# aw_601_pongclock.net
KiCad netlist of a schematic drawn in EAGLE
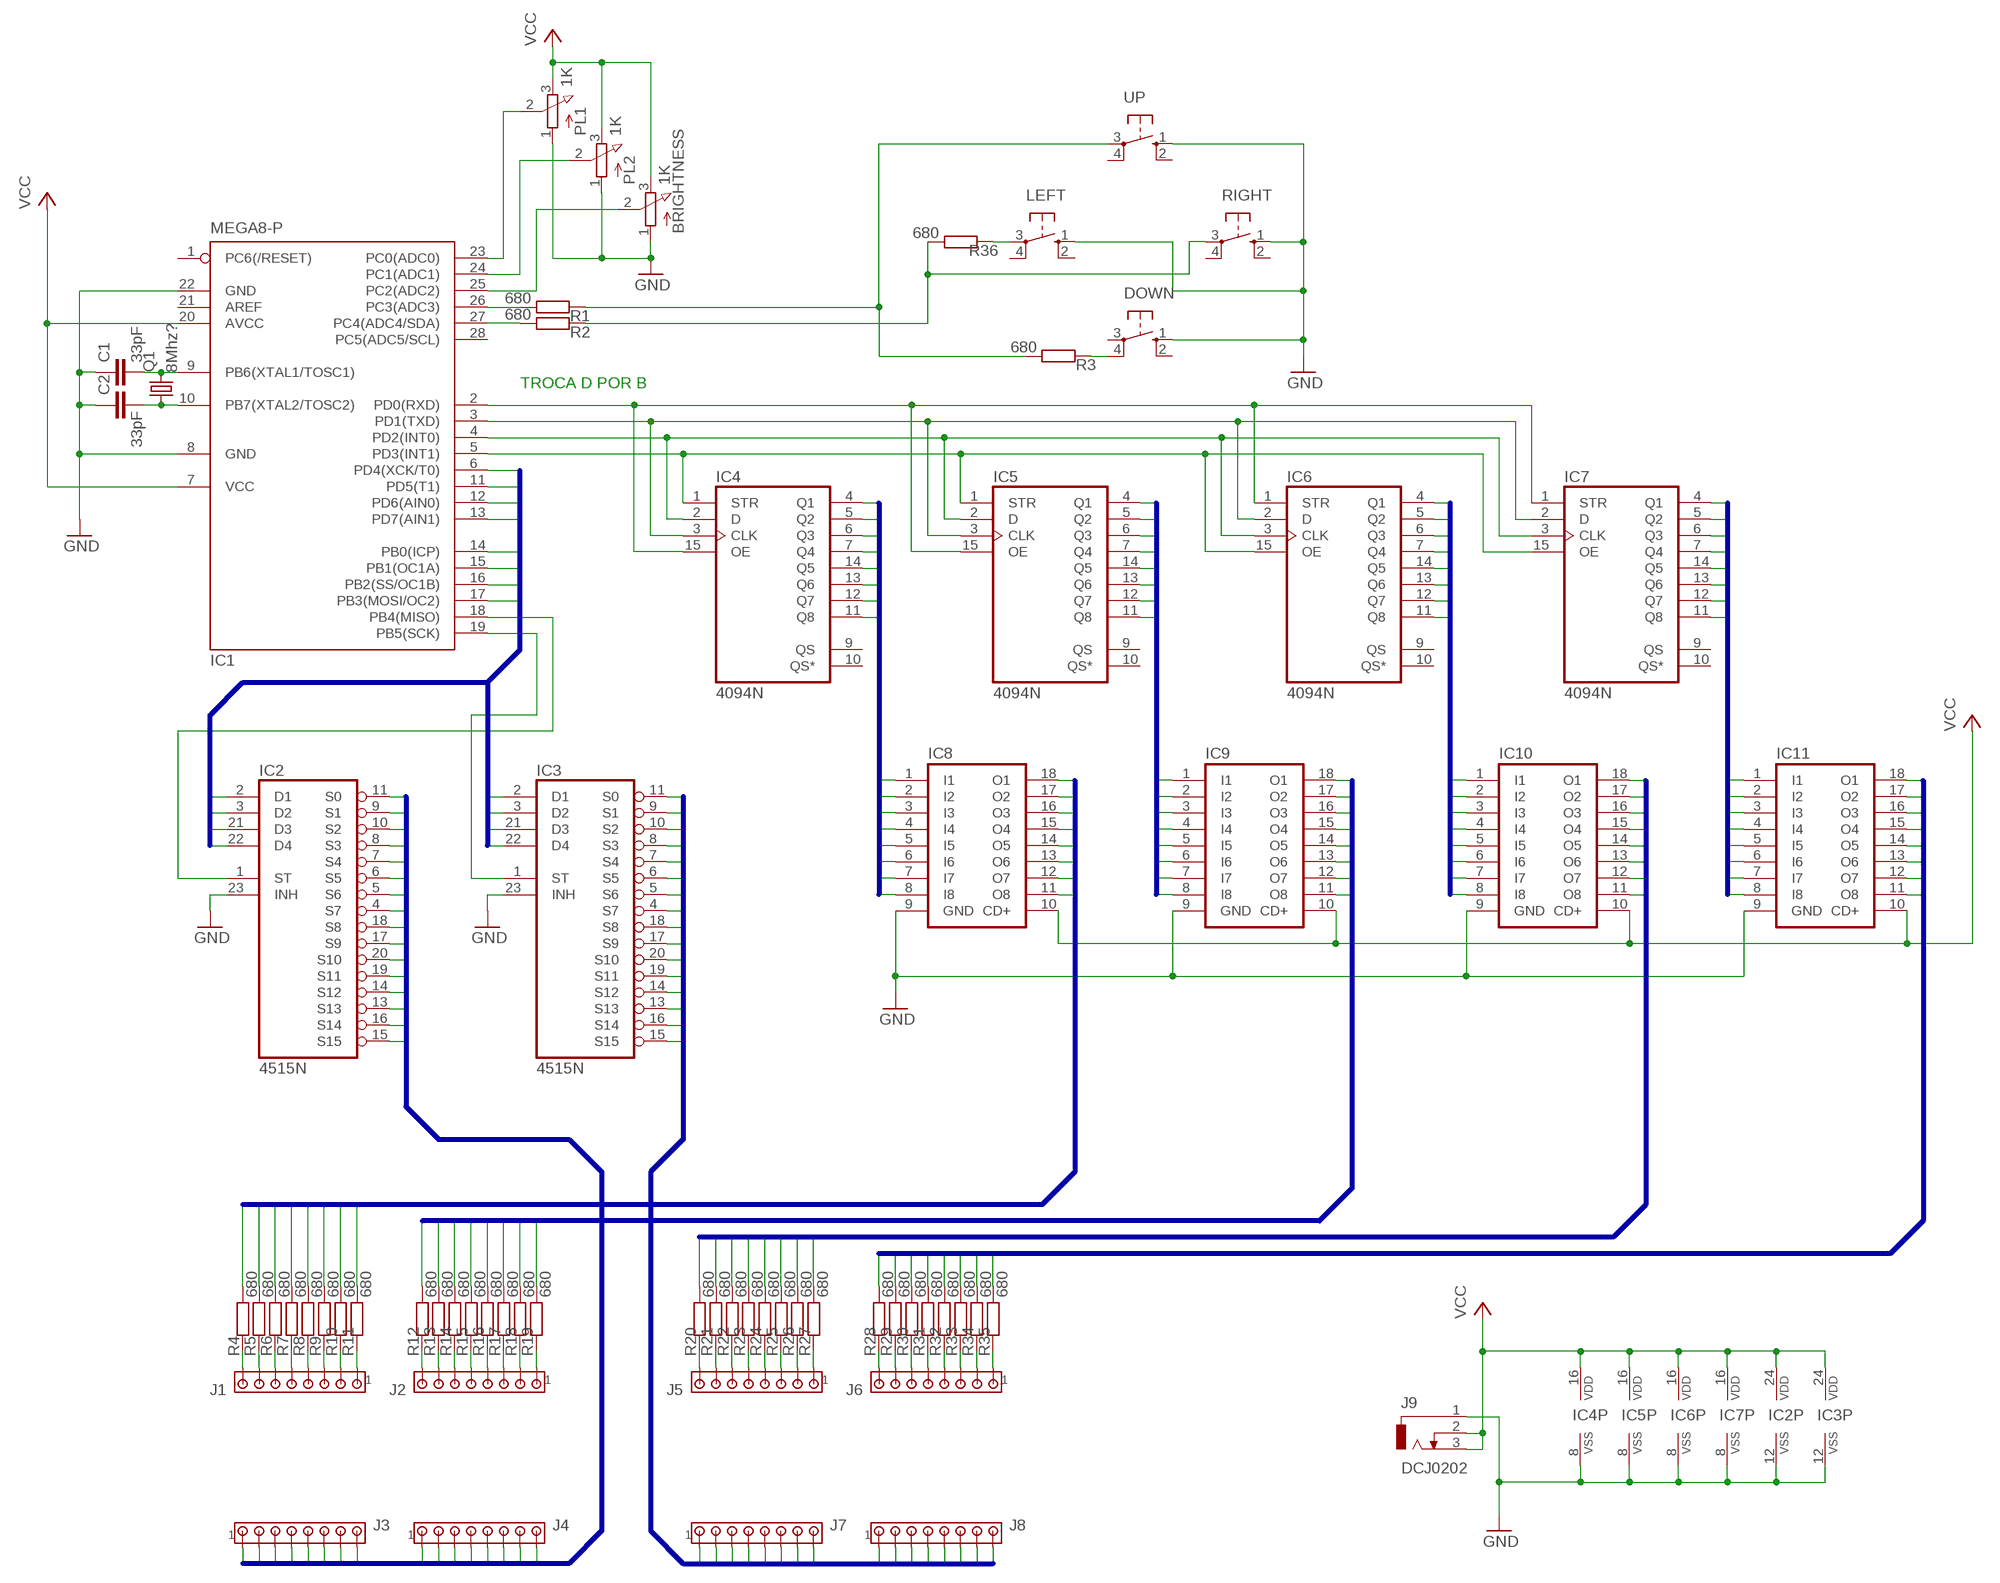
[diagram p0: schematic, sheet 1]

(export (version "E")
  (design (tool "Eeschema 10.0.6"))
  (components
    (comp (ref "BRIGHTNESS")
      (value "1K")
      (footprint "eagle-import:3RP_1610N")
      (libsource (lib "eagle-import") (part "3RP/1610N"))
    )
    (comp (ref "C1")
      (value "33pF")
      (footprint "eagle-import:C025-025X050")
      (libsource (lib "eagle-import") (part "C-EU025-025X050"))
    )
    (comp (ref "C2")
      (value "33pF")
      (footprint "eagle-import:C025-025X050")
      (libsource (lib "eagle-import") (part "C-EU025-025X050"))
    )
    (comp (ref "DOWN")
      (value "40/XX")
      (footprint "eagle-import:B3F_40XX")
      (libsource (lib "eagle-import") (part "40/XX"))
    )
    (comp (ref "IC1")
      (value "MEGA8-P")
      (footprint "eagle-import:DIL28-3")
      (libsource (lib "eagle-import") (part "MEGA8-P"))
    )
    (comp (ref "IC2")
      (value "4515N")
      (footprint "eagle-import:DIL24-6")
      (libsource (lib "eagle-import") (part "4515N"))
    )
    (comp (ref "IC3")
      (value "4515N")
      (footprint "eagle-import:DIL24-6")
      (libsource (lib "eagle-import") (part "4515N"))
    )
    (comp (ref "IC4")
      (value "4094N")
      (footprint "eagle-import:DIL16")
      (libsource (lib "eagle-import") (part "4094N"))
    )
    (comp (ref "IC5")
      (value "4094N")
      (footprint "eagle-import:DIL16")
      (libsource (lib "eagle-import") (part "4094N"))
    )
    (comp (ref "IC6")
      (value "4094N")
      (footprint "eagle-import:DIL16")
      (libsource (lib "eagle-import") (part "4094N"))
    )
    (comp (ref "IC7")
      (value "4094N")
      (footprint "eagle-import:DIL16")
      (libsource (lib "eagle-import") (part "4094N"))
    )
    (comp (ref "IC8")
      (value "ULN2803A")
      (footprint "eagle-import:DIL18")
      (libsource (lib "eagle-import") (part "ULN2803A"))
    )
    (comp (ref "IC9")
      (value "ULN2803A")
      (footprint "eagle-import:DIL18")
      (libsource (lib "eagle-import") (part "ULN2803A"))
    )
    (comp (ref "IC10")
      (value "ULN2803A")
      (footprint "eagle-import:DIL18")
      (libsource (lib "eagle-import") (part "ULN2803A"))
    )
    (comp (ref "IC11")
      (value "ULN2803A")
      (footprint "eagle-import:DIL18")
      (libsource (lib "eagle-import") (part "ULN2803A"))
    )
    (comp (ref "J1")
      (value "MTA08-100")
      (footprint "eagle-import:10X08MTA")
      (libsource (lib "eagle-import") (part "MTA08-100"))
    )
    (comp (ref "J2")
      (value "MTA08-100")
      (footprint "eagle-import:10X08MTA")
      (libsource (lib "eagle-import") (part "MTA08-100"))
    )
    (comp (ref "J3")
      (value "MTA08-100")
      (footprint "eagle-import:10X08MTA")
      (libsource (lib "eagle-import") (part "MTA08-100"))
    )
    (comp (ref "J4")
      (value "MTA08-100")
      (footprint "eagle-import:10X08MTA")
      (libsource (lib "eagle-import") (part "MTA08-100"))
    )
    (comp (ref "J5")
      (value "MTA08-100")
      (footprint "eagle-import:10X08MTA")
      (libsource (lib "eagle-import") (part "MTA08-100"))
    )
    (comp (ref "J6")
      (value "MTA08-100")
      (footprint "eagle-import:10X08MTA")
      (libsource (lib "eagle-import") (part "MTA08-100"))
    )
    (comp (ref "J7")
      (value "MTA08-100")
      (footprint "eagle-import:10X08MTA")
      (libsource (lib "eagle-import") (part "MTA08-100"))
    )
    (comp (ref "J8")
      (value "MTA08-100")
      (footprint "eagle-import:10X08MTA")
      (libsource (lib "eagle-import") (part "MTA08-100"))
    )
    (comp (ref "J9")
      (value "DCJ0202")
      (footprint "eagle-import:DCJ0202")
      (libsource (lib "eagle-import") (part "DCJ0202"))
    )
    (comp (ref "LEFT")
      (value "40/XX")
      (footprint "eagle-import:B3F_40XX")
      (libsource (lib "eagle-import") (part "40/XX"))
    )
    (comp (ref "PL1")
      (value "1K")
      (footprint "eagle-import:3RP_1610N")
      (libsource (lib "eagle-import") (part "3RP/1610N"))
    )
    (comp (ref "PL2")
      (value "1K")
      (footprint "eagle-import:3RP_1610N")
      (libsource (lib "eagle-import") (part "3RP/1610N"))
    )
    (comp (ref "Q1")
      (value "8Mhz?")
      (footprint "eagle-import:HC49U70")
      (libsource (lib "eagle-import") (part "CRYSTALHC49U70"))
    )
    (comp (ref "R1")
      (value "680")
      (footprint "eagle-import:0207_10")
      (libsource (lib "eagle-import") (part "R-EU_0207/10"))
    )
    (comp (ref "R2")
      (value "680")
      (footprint "eagle-import:0207_10")
      (libsource (lib "eagle-import") (part "R-EU_0207/10"))
    )
    (comp (ref "R3")
      (value "680")
      (footprint "eagle-import:0207_10")
      (libsource (lib "eagle-import") (part "R-EU_0207/10"))
    )
    (comp (ref "R4")
      (value "680")
      (footprint "eagle-import:0207_10")
      (libsource (lib "eagle-import") (part "R-EU_0207/10"))
    )
    (comp (ref "R5")
      (value "680")
      (footprint "eagle-import:0207_10")
      (libsource (lib "eagle-import") (part "R-EU_0207/10"))
    )
    (comp (ref "R6")
      (value "680")
      (footprint "eagle-import:0207_10")
      (libsource (lib "eagle-import") (part "R-EU_0207/10"))
    )
    (comp (ref "R7")
      (value "680")
      (footprint "eagle-import:0207_10")
      (libsource (lib "eagle-import") (part "R-EU_0207/10"))
    )
    (comp (ref "R8")
      (value "680")
      (footprint "eagle-import:0207_10")
      (libsource (lib "eagle-import") (part "R-EU_0207/10"))
    )
    (comp (ref "R9")
      (value "680")
      (footprint "eagle-import:0207_10")
      (libsource (lib "eagle-import") (part "R-EU_0207/10"))
    )
    (comp (ref "R10")
      (value "680")
      (footprint "eagle-import:0207_10")
      (libsource (lib "eagle-import") (part "R-EU_0207/10"))
    )
    (comp (ref "R11")
      (value "680")
      (footprint "eagle-import:0207_10")
      (libsource (lib "eagle-import") (part "R-EU_0207/10"))
    )
    (comp (ref "R12")
      (value "680")
      (footprint "eagle-import:0207_10")
      (libsource (lib "eagle-import") (part "R-EU_0207/10"))
    )
    (comp (ref "R13")
      (value "680")
      (footprint "eagle-import:0207_10")
      (libsource (lib "eagle-import") (part "R-EU_0207/10"))
    )
    (comp (ref "R14")
      (value "680")
      (footprint "eagle-import:0207_10")
      (libsource (lib "eagle-import") (part "R-EU_0207/10"))
    )
    (comp (ref "R15")
      (value "680")
      (footprint "eagle-import:0207_10")
      (libsource (lib "eagle-import") (part "R-EU_0207/10"))
    )
    (comp (ref "R16")
      (value "680")
      (footprint "eagle-import:0207_10")
      (libsource (lib "eagle-import") (part "R-EU_0207/10"))
    )
    (comp (ref "R17")
      (value "680")
      (footprint "eagle-import:0207_10")
      (libsource (lib "eagle-import") (part "R-EU_0207/10"))
    )
    (comp (ref "R18")
      (value "680")
      (footprint "eagle-import:0207_10")
      (libsource (lib "eagle-import") (part "R-EU_0207/10"))
    )
    (comp (ref "R19")
      (value "680")
      (footprint "eagle-import:0207_10")
      (libsource (lib "eagle-import") (part "R-EU_0207/10"))
    )
    (comp (ref "R20")
      (value "680")
      (footprint "eagle-import:0207_10")
      (libsource (lib "eagle-import") (part "R-EU_0207/10"))
    )
    (comp (ref "R21")
      (value "680")
      (footprint "eagle-import:0207_10")
      (libsource (lib "eagle-import") (part "R-EU_0207/10"))
    )
    (comp (ref "R22")
      (value "680")
      (footprint "eagle-import:0207_10")
      (libsource (lib "eagle-import") (part "R-EU_0207/10"))
    )
    (comp (ref "R23")
      (value "680")
      (footprint "eagle-import:0207_10")
      (libsource (lib "eagle-import") (part "R-EU_0207/10"))
    )
    (comp (ref "R24")
      (value "680")
      (footprint "eagle-import:0207_10")
      (libsource (lib "eagle-import") (part "R-EU_0207/10"))
    )
    (comp (ref "R25")
      (value "680")
      (footprint "eagle-import:0207_10")
      (libsource (lib "eagle-import") (part "R-EU_0207/10"))
    )
    (comp (ref "R26")
      (value "680")
      (footprint "eagle-import:0207_10")
      (libsource (lib "eagle-import") (part "R-EU_0207/10"))
    )
    (comp (ref "R27")
      (value "680")
      (footprint "eagle-import:0207_10")
      (libsource (lib "eagle-import") (part "R-EU_0207/10"))
    )
    (comp (ref "R28")
      (value "680")
      (footprint "eagle-import:0207_10")
      (libsource (lib "eagle-import") (part "R-EU_0207/10"))
    )
    (comp (ref "R29")
      (value "680")
      (footprint "eagle-import:0207_10")
      (libsource (lib "eagle-import") (part "R-EU_0207/10"))
    )
    (comp (ref "R30")
      (value "680")
      (footprint "eagle-import:0207_10")
      (libsource (lib "eagle-import") (part "R-EU_0207/10"))
    )
    (comp (ref "R31")
      (value "680")
      (footprint "eagle-import:0207_10")
      (libsource (lib "eagle-import") (part "R-EU_0207/10"))
    )
    (comp (ref "R32")
      (value "680")
      (footprint "eagle-import:0207_10")
      (libsource (lib "eagle-import") (part "R-EU_0207/10"))
    )
    (comp (ref "R33")
      (value "680")
      (footprint "eagle-import:0207_10")
      (libsource (lib "eagle-import") (part "R-EU_0207/10"))
    )
    (comp (ref "R34")
      (value "680")
      (footprint "eagle-import:0207_10")
      (libsource (lib "eagle-import") (part "R-EU_0207/10"))
    )
    (comp (ref "R35")
      (value "680")
      (footprint "eagle-import:0207_10")
      (libsource (lib "eagle-import") (part "R-EU_0207/10"))
    )
    (comp (ref "R36")
      (value "680")
      (footprint "eagle-import:0207_10")
      (libsource (lib "eagle-import") (part "R-EU_0207/10"))
    )
    (comp (ref "RIGHT")
      (value "40/XX")
      (footprint "eagle-import:B3F_40XX")
      (libsource (lib "eagle-import") (part "40/XX"))
    )
    (comp (ref "UP")
      (value "40/XX")
      (footprint "eagle-import:B3F_40XX")
      (libsource (lib "eagle-import") (part "40/XX"))
    )
  )
  (nets
    (net (code "1") (name "/CATH1_0") (class "Default")
      (node (ref "IC2") (pin "11") (pinfunction "S0_11") (pintype "output"))
      (node (ref "J3") (pin "1") (pinfunction "1_1") (pintype "passive"))
    )
    (net (code "2") (name "/CATH1_1") (class "Default")
      (node (ref "IC2") (pin "9") (pinfunction "S1_9") (pintype "output"))
      (node (ref "J3") (pin "2") (pinfunction "2_2") (pintype "passive"))
    )
    (net (code "3") (name "/CATH1_2") (class "Default")
      (node (ref "IC2") (pin "10") (pinfunction "S2_10") (pintype "output"))
      (node (ref "J3") (pin "3") (pinfunction "3_3") (pintype "passive"))
    )
    (net (code "4") (name "/CATH1_3") (class "Default")
      (node (ref "IC2") (pin "8") (pinfunction "S3_8") (pintype "output"))
      (node (ref "J3") (pin "4") (pinfunction "4_4") (pintype "passive"))
    )
    (net (code "5") (name "/CATH1_4") (class "Default")
      (node (ref "IC2") (pin "7") (pinfunction "S4_7") (pintype "output"))
      (node (ref "J3") (pin "5") (pinfunction "5_5") (pintype "passive"))
    )
    (net (code "6") (name "/CATH1_5") (class "Default")
      (node (ref "IC2") (pin "6") (pinfunction "S5_6") (pintype "output"))
      (node (ref "J3") (pin "6") (pinfunction "6_6") (pintype "passive"))
    )
    (net (code "7") (name "/CATH1_6") (class "Default")
      (node (ref "IC2") (pin "5") (pinfunction "S6_5") (pintype "output"))
      (node (ref "J3") (pin "7") (pinfunction "7_7") (pintype "passive"))
    )
    (net (code "8") (name "/CATH1_7") (class "Default")
      (node (ref "IC2") (pin "4") (pinfunction "S7_4") (pintype "output"))
      (node (ref "J3") (pin "8") (pinfunction "8_8") (pintype "passive"))
    )
    (net (code "9") (name "/CATH1_8") (class "Default")
      (node (ref "IC2") (pin "18") (pinfunction "S8_18") (pintype "output"))
      (node (ref "J4") (pin "1") (pinfunction "1_1") (pintype "passive"))
    )
    (net (code "10") (name "/CATH1_9") (class "Default")
      (node (ref "IC2") (pin "17") (pinfunction "S9_17") (pintype "output"))
      (node (ref "J4") (pin "2") (pinfunction "2_2") (pintype "passive"))
    )
    (net (code "11") (name "/CATH1_10") (class "Default")
      (node (ref "IC2") (pin "20") (pinfunction "S10_20") (pintype "output"))
      (node (ref "J4") (pin "3") (pinfunction "3_3") (pintype "passive"))
    )
    (net (code "12") (name "/CATH1_11") (class "Default")
      (node (ref "IC2") (pin "19") (pinfunction "S11_19") (pintype "output"))
      (node (ref "J4") (pin "4") (pinfunction "4_4") (pintype "passive"))
    )
    (net (code "13") (name "/CATH1_12") (class "Default")
      (node (ref "IC2") (pin "14") (pinfunction "S12_14") (pintype "output"))
      (node (ref "J4") (pin "5") (pinfunction "5_5") (pintype "passive"))
    )
    (net (code "14") (name "/CATH1_13") (class "Default")
      (node (ref "IC2") (pin "13") (pinfunction "S13_13") (pintype "output"))
      (node (ref "J4") (pin "6") (pinfunction "6_6") (pintype "passive"))
    )
    (net (code "15") (name "/CATH1_14") (class "Default")
      (node (ref "IC2") (pin "16") (pinfunction "S14_16") (pintype "output"))
      (node (ref "J4") (pin "7") (pinfunction "7_7") (pintype "passive"))
    )
    (net (code "16") (name "/CATH1_15") (class "Default")
      (node (ref "IC2") (pin "15") (pinfunction "S15_15") (pintype "output"))
      (node (ref "J4") (pin "8") (pinfunction "8_8") (pintype "passive"))
    )
    (net (code "17") (name "/CATH2_0") (class "Default")
      (node (ref "IC3") (pin "11") (pinfunction "S0_11") (pintype "output"))
      (node (ref "J7") (pin "1") (pinfunction "1_1") (pintype "passive"))
    )
    (net (code "18") (name "/CATH2_1") (class "Default")
      (node (ref "IC3") (pin "9") (pinfunction "S1_9") (pintype "output"))
      (node (ref "J7") (pin "2") (pinfunction "2_2") (pintype "passive"))
    )
    (net (code "19") (name "/CATH2_2") (class "Default")
      (node (ref "IC3") (pin "10") (pinfunction "S2_10") (pintype "output"))
      (node (ref "J7") (pin "3") (pinfunction "3_3") (pintype "passive"))
    )
    (net (code "20") (name "/CATH2_3") (class "Default")
      (node (ref "IC3") (pin "8") (pinfunction "S3_8") (pintype "output"))
      (node (ref "J7") (pin "4") (pinfunction "4_4") (pintype "passive"))
    )
    (net (code "21") (name "/CATH2_4") (class "Default")
      (node (ref "IC3") (pin "7") (pinfunction "S4_7") (pintype "output"))
      (node (ref "J7") (pin "5") (pinfunction "5_5") (pintype "passive"))
    )
    (net (code "22") (name "/CATH2_5") (class "Default")
      (node (ref "IC3") (pin "6") (pinfunction "S5_6") (pintype "output"))
      (node (ref "J7") (pin "6") (pinfunction "6_6") (pintype "passive"))
    )
    (net (code "23") (name "/CATH2_6") (class "Default")
      (node (ref "IC3") (pin "5") (pinfunction "S6_5") (pintype "output"))
      (node (ref "J7") (pin "7") (pinfunction "7_7") (pintype "passive"))
    )
    (net (code "24") (name "/CATH2_7") (class "Default")
      (node (ref "IC3") (pin "4") (pinfunction "S7_4") (pintype "output"))
      (node (ref "J7") (pin "8") (pinfunction "8_8") (pintype "passive"))
    )
    (net (code "25") (name "/CATH2_8") (class "Default")
      (node (ref "IC3") (pin "18") (pinfunction "S8_18") (pintype "output"))
      (node (ref "J8") (pin "1") (pinfunction "1_1") (pintype "passive"))
    )
    (net (code "26") (name "/CATH2_9") (class "Default")
      (node (ref "IC3") (pin "17") (pinfunction "S9_17") (pintype "output"))
      (node (ref "J8") (pin "2") (pinfunction "2_2") (pintype "passive"))
    )
    (net (code "27") (name "/CATH2_10") (class "Default")
      (node (ref "IC3") (pin "20") (pinfunction "S10_20") (pintype "output"))
      (node (ref "J8") (pin "3") (pinfunction "3_3") (pintype "passive"))
    )
    (net (code "28") (name "/CATH2_11") (class "Default")
      (node (ref "IC3") (pin "19") (pinfunction "S11_19") (pintype "output"))
      (node (ref "J8") (pin "4") (pinfunction "4_4") (pintype "passive"))
    )
    (net (code "29") (name "/CATH2_12") (class "Default")
      (node (ref "IC3") (pin "14") (pinfunction "S12_14") (pintype "output"))
      (node (ref "J8") (pin "5") (pinfunction "5_5") (pintype "passive"))
    )
    (net (code "30") (name "/CATH2_13") (class "Default")
      (node (ref "IC3") (pin "13") (pinfunction "S13_13") (pintype "output"))
      (node (ref "J8") (pin "6") (pinfunction "6_6") (pintype "passive"))
    )
    (net (code "31") (name "/CATH2_14") (class "Default")
      (node (ref "IC3") (pin "16") (pinfunction "S14_16") (pintype "output"))
      (node (ref "J8") (pin "7") (pinfunction "7_7") (pintype "passive"))
    )
    (net (code "32") (name "/CATH2_15") (class "Default")
      (node (ref "IC3") (pin "15") (pinfunction "S15_15") (pintype "output"))
      (node (ref "J8") (pin "8") (pinfunction "8_8") (pintype "passive"))
    )
    (net (code "33") (name "/LED1A1") (class "Default")
      (node (ref "IC4") (pin "4") (pinfunction "Q1_4") (pintype "output"))
      (node (ref "IC8") (pin "1") (pinfunction "I1_1") (pintype "input"))
    )
    (net (code "34") (name "/LED1A2") (class "Default")
      (node (ref "IC4") (pin "5") (pinfunction "Q2_5") (pintype "output"))
      (node (ref "IC8") (pin "2") (pinfunction "I2_2") (pintype "input"))
    )
    (net (code "35") (name "/LED1A3") (class "Default")
      (node (ref "IC4") (pin "6") (pinfunction "Q3_6") (pintype "output"))
      (node (ref "IC8") (pin "3") (pinfunction "I3_3") (pintype "input"))
    )
    (net (code "36") (name "/LED1A4") (class "Default")
      (node (ref "IC4") (pin "7") (pinfunction "Q4_7") (pintype "output"))
      (node (ref "IC8") (pin "4") (pinfunction "I4_4") (pintype "input"))
    )
    (net (code "37") (name "/LED1A5") (class "Default")
      (node (ref "IC4") (pin "14") (pinfunction "Q5_14") (pintype "output"))
      (node (ref "IC8") (pin "5") (pinfunction "I5_5") (pintype "input"))
    )
    (net (code "38") (name "/LED1A6") (class "Default")
      (node (ref "IC4") (pin "13") (pinfunction "Q6_13") (pintype "output"))
      (node (ref "IC8") (pin "6") (pinfunction "I6_6") (pintype "input"))
    )
    (net (code "39") (name "/LED1A7") (class "Default")
      (node (ref "IC4") (pin "12") (pinfunction "Q7_12") (pintype "output"))
      (node (ref "IC8") (pin "7") (pinfunction "I7_7") (pintype "input"))
    )
    (net (code "40") (name "/LED1A8") (class "Default")
      (node (ref "IC4") (pin "11") (pinfunction "Q8_11") (pintype "output"))
      (node (ref "IC8") (pin "8") (pinfunction "I8_8") (pintype "input"))
    )
    (net (code "41") (name "/LED1B1") (class "Default")
      (node (ref "IC5") (pin "4") (pinfunction "Q1_4") (pintype "output"))
      (node (ref "IC9") (pin "1") (pinfunction "I1_1") (pintype "input"))
    )
    (net (code "42") (name "/LED1B2") (class "Default")
      (node (ref "IC5") (pin "5") (pinfunction "Q2_5") (pintype "output"))
      (node (ref "IC9") (pin "2") (pinfunction "I2_2") (pintype "input"))
    )
    (net (code "43") (name "/LED1B3") (class "Default")
      (node (ref "IC5") (pin "6") (pinfunction "Q3_6") (pintype "output"))
      (node (ref "IC9") (pin "3") (pinfunction "I3_3") (pintype "input"))
    )
    (net (code "44") (name "/LED1B4") (class "Default")
      (node (ref "IC5") (pin "7") (pinfunction "Q4_7") (pintype "output"))
      (node (ref "IC9") (pin "4") (pinfunction "I4_4") (pintype "input"))
    )
    (net (code "45") (name "/LED1B5") (class "Default")
      (node (ref "IC5") (pin "14") (pinfunction "Q5_14") (pintype "output"))
      (node (ref "IC9") (pin "5") (pinfunction "I5_5") (pintype "input"))
    )
    (net (code "46") (name "/LED1B6") (class "Default")
      (node (ref "IC5") (pin "13") (pinfunction "Q6_13") (pintype "output"))
      (node (ref "IC9") (pin "6") (pinfunction "I6_6") (pintype "input"))
    )
    (net (code "47") (name "/LED1B7") (class "Default")
      (node (ref "IC5") (pin "12") (pinfunction "Q7_12") (pintype "output"))
      (node (ref "IC9") (pin "7") (pinfunction "I7_7") (pintype "input"))
    )
    (net (code "48") (name "/LED1B8") (class "Default")
      (node (ref "IC5") (pin "11") (pinfunction "Q8_11") (pintype "output"))
      (node (ref "IC9") (pin "8") (pinfunction "I8_8") (pintype "input"))
    )
    (net (code "49") (name "/LED2A1") (class "Default")
      (node (ref "IC10") (pin "1") (pinfunction "I1_1") (pintype "input"))
      (node (ref "IC6") (pin "4") (pinfunction "Q1_4") (pintype "output"))
    )
    (net (code "50") (name "/LED2A2") (class "Default")
      (node (ref "IC10") (pin "2") (pinfunction "I2_2") (pintype "input"))
      (node (ref "IC6") (pin "5") (pinfunction "Q2_5") (pintype "output"))
    )
    (net (code "51") (name "/LED2A3") (class "Default")
      (node (ref "IC10") (pin "3") (pinfunction "I3_3") (pintype "input"))
      (node (ref "IC6") (pin "6") (pinfunction "Q3_6") (pintype "output"))
    )
    (net (code "52") (name "/LED2A4") (class "Default")
      (node (ref "IC10") (pin "4") (pinfunction "I4_4") (pintype "input"))
      (node (ref "IC6") (pin "7") (pinfunction "Q4_7") (pintype "output"))
    )
    (net (code "53") (name "/LED2A5") (class "Default")
      (node (ref "IC10") (pin "5") (pinfunction "I5_5") (pintype "input"))
      (node (ref "IC6") (pin "14") (pinfunction "Q5_14") (pintype "output"))
    )
    (net (code "54") (name "/LED2A6") (class "Default")
      (node (ref "IC10") (pin "6") (pinfunction "I6_6") (pintype "input"))
      (node (ref "IC6") (pin "13") (pinfunction "Q6_13") (pintype "output"))
    )
    (net (code "55") (name "/LED2A7") (class "Default")
      (node (ref "IC10") (pin "7") (pinfunction "I7_7") (pintype "input"))
      (node (ref "IC6") (pin "12") (pinfunction "Q7_12") (pintype "output"))
    )
    (net (code "56") (name "/LED2A8") (class "Default")
      (node (ref "IC10") (pin "8") (pinfunction "I8_8") (pintype "input"))
      (node (ref "IC6") (pin "11") (pinfunction "Q8_11") (pintype "output"))
    )
    (net (code "57") (name "/LED2B1") (class "Default")
      (node (ref "IC11") (pin "1") (pinfunction "I1_1") (pintype "input"))
      (node (ref "IC7") (pin "4") (pinfunction "Q1_4") (pintype "output"))
    )
    (net (code "58") (name "/LED2B2") (class "Default")
      (node (ref "IC11") (pin "2") (pinfunction "I2_2") (pintype "input"))
      (node (ref "IC7") (pin "5") (pinfunction "Q2_5") (pintype "output"))
    )
    (net (code "59") (name "/LED2B3") (class "Default")
      (node (ref "IC11") (pin "3") (pinfunction "I3_3") (pintype "input"))
      (node (ref "IC7") (pin "6") (pinfunction "Q3_6") (pintype "output"))
    )
    (net (code "60") (name "/LED2B4") (class "Default")
      (node (ref "IC11") (pin "4") (pinfunction "I4_4") (pintype "input"))
      (node (ref "IC7") (pin "7") (pinfunction "Q4_7") (pintype "output"))
    )
    (net (code "61") (name "/LED2B5") (class "Default")
      (node (ref "IC11") (pin "5") (pinfunction "I5_5") (pintype "input"))
      (node (ref "IC7") (pin "14") (pinfunction "Q5_14") (pintype "output"))
    )
    (net (code "62") (name "/LED2B6") (class "Default")
      (node (ref "IC11") (pin "6") (pinfunction "I6_6") (pintype "input"))
      (node (ref "IC7") (pin "13") (pinfunction "Q6_13") (pintype "output"))
    )
    (net (code "63") (name "/LED2B7") (class "Default")
      (node (ref "IC11") (pin "7") (pinfunction "I7_7") (pintype "input"))
      (node (ref "IC7") (pin "12") (pinfunction "Q7_12") (pintype "output"))
    )
    (net (code "64") (name "/LED2B8") (class "Default")
      (node (ref "IC11") (pin "8") (pinfunction "I8_8") (pintype "input"))
      (node (ref "IC7") (pin "11") (pinfunction "Q8_11") (pintype "output"))
    )
    (net (code "65") (name "/LEDGND0") (class "Default")
      (node (ref "IC1") (pin "6") (pinfunction "PD4(XCK/T0)_6") (pintype "bidirectional"))
      (node (ref "IC2") (pin "2") (pinfunction "D1_2") (pintype "input"))
    )
    (net (code "66") (name "/LEDGND1") (class "Default")
      (node (ref "IC1") (pin "11") (pinfunction "PD5(T1)_11") (pintype "bidirectional"))
      (node (ref "IC2") (pin "3") (pinfunction "D2_3") (pintype "input"))
    )
    (net (code "67") (name "/LEDGND2") (class "Default")
      (node (ref "IC1") (pin "12") (pinfunction "PD6(AIN0)_12") (pintype "bidirectional"))
      (node (ref "IC2") (pin "21") (pinfunction "D3_21") (pintype "input"))
    )
    (net (code "68") (name "/LEDGND3") (class "Default")
      (node (ref "IC1") (pin "13") (pinfunction "PD7(AIN1)_13") (pintype "bidirectional"))
      (node (ref "IC2") (pin "22") (pinfunction "D4_22") (pintype "input"))
    )
    (net (code "69") (name "/LEDGND4") (class "Default")
      (node (ref "IC1") (pin "14") (pinfunction "PB0(ICP)_14") (pintype "bidirectional"))
      (node (ref "IC3") (pin "2") (pinfunction "D1_2") (pintype "input"))
    )
    (net (code "70") (name "/LEDGND5") (class "Default")
      (node (ref "IC1") (pin "15") (pinfunction "PB1(OC1A)_15") (pintype "bidirectional"))
      (node (ref "IC3") (pin "3") (pinfunction "D2_3") (pintype "input"))
    )
    (net (code "71") (name "/LEDGND6") (class "Default")
      (node (ref "IC1") (pin "16") (pinfunction "PB2(SS/OC1B)_16") (pintype "bidirectional"))
      (node (ref "IC3") (pin "21") (pinfunction "D3_21") (pintype "input"))
    )
    (net (code "72") (name "/LEDGND7") (class "Default")
      (node (ref "IC1") (pin "17") (pinfunction "PB3(MOSI/OC2)_17") (pintype "bidirectional"))
      (node (ref "IC3") (pin "22") (pinfunction "D4_22") (pintype "input"))
    )
    (net (code "73") (name "/TRAN1A1") (class "Default")
      (node (ref "IC8") (pin "18") (pinfunction "O1_18") (pintype "open_collector"))
      (node (ref "R4") (pin "2") (pinfunction "2_2") (pintype "passive"))
    )
    (net (code "74") (name "/TRAN1A2") (class "Default")
      (node (ref "IC8") (pin "17") (pinfunction "O2_17") (pintype "open_collector"))
      (node (ref "R5") (pin "2") (pinfunction "2_2") (pintype "passive"))
    )
    (net (code "75") (name "/TRAN1A3") (class "Default")
      (node (ref "IC8") (pin "16") (pinfunction "O3_16") (pintype "open_collector"))
      (node (ref "R6") (pin "2") (pinfunction "2_2") (pintype "passive"))
    )
    (net (code "76") (name "/TRAN1A4") (class "Default")
      (node (ref "IC8") (pin "15") (pinfunction "O4_15") (pintype "open_collector"))
      (node (ref "R7") (pin "2") (pinfunction "2_2") (pintype "passive"))
    )
    (net (code "77") (name "/TRAN1A5") (class "Default")
      (node (ref "IC8") (pin "14") (pinfunction "O5_14") (pintype "open_collector"))
      (node (ref "R8") (pin "2") (pinfunction "2_2") (pintype "passive"))
    )
    (net (code "78") (name "/TRAN1A6") (class "Default")
      (node (ref "IC8") (pin "13") (pinfunction "O6_13") (pintype "open_collector"))
      (node (ref "R9") (pin "2") (pinfunction "2_2") (pintype "passive"))
    )
    (net (code "79") (name "/TRAN1A7") (class "Default")
      (node (ref "IC8") (pin "12") (pinfunction "O7_12") (pintype "open_collector"))
      (node (ref "R10") (pin "2") (pinfunction "2_2") (pintype "passive"))
    )
    (net (code "80") (name "/TRAN1A8") (class "Default")
      (node (ref "IC8") (pin "11") (pinfunction "O8_11") (pintype "open_collector"))
      (node (ref "R11") (pin "2") (pinfunction "2_2") (pintype "passive"))
    )
    (net (code "81") (name "/TRAN1B1") (class "Default")
      (node (ref "IC10") (pin "18") (pinfunction "O1_18") (pintype "open_collector"))
      (node (ref "R20") (pin "2") (pinfunction "2_2") (pintype "passive"))
    )
    (net (code "82") (name "/TRAN1B2") (class "Default")
      (node (ref "IC10") (pin "17") (pinfunction "O2_17") (pintype "open_collector"))
      (node (ref "R21") (pin "2") (pinfunction "2_2") (pintype "passive"))
    )
    (net (code "83") (name "/TRAN1B3") (class "Default")
      (node (ref "IC10") (pin "16") (pinfunction "O3_16") (pintype "open_collector"))
      (node (ref "R22") (pin "2") (pinfunction "2_2") (pintype "passive"))
    )
    (net (code "84") (name "/TRAN1B4") (class "Default")
      (node (ref "IC10") (pin "15") (pinfunction "O4_15") (pintype "open_collector"))
      (node (ref "R23") (pin "2") (pinfunction "2_2") (pintype "passive"))
    )
    (net (code "85") (name "/TRAN1B5") (class "Default")
      (node (ref "IC10") (pin "14") (pinfunction "O5_14") (pintype "open_collector"))
      (node (ref "R24") (pin "2") (pinfunction "2_2") (pintype "passive"))
    )
    (net (code "86") (name "/TRAN1B6") (class "Default")
      (node (ref "IC10") (pin "13") (pinfunction "O6_13") (pintype "open_collector"))
      (node (ref "R25") (pin "2") (pinfunction "2_2") (pintype "passive"))
    )
    (net (code "87") (name "/TRAN1B7") (class "Default")
      (node (ref "IC10") (pin "12") (pinfunction "O7_12") (pintype "open_collector"))
      (node (ref "R26") (pin "2") (pinfunction "2_2") (pintype "passive"))
    )
    (net (code "88") (name "/TRAN1B8") (class "Default")
      (node (ref "IC10") (pin "11") (pinfunction "O8_11") (pintype "open_collector"))
      (node (ref "R27") (pin "2") (pinfunction "2_2") (pintype "passive"))
    )
    (net (code "89") (name "/TRAN2A1") (class "Default")
      (node (ref "IC9") (pin "18") (pinfunction "O1_18") (pintype "open_collector"))
      (node (ref "R12") (pin "2") (pinfunction "2_2") (pintype "passive"))
    )
    (net (code "90") (name "/TRAN2A2") (class "Default")
      (node (ref "IC9") (pin "17") (pinfunction "O2_17") (pintype "open_collector"))
      (node (ref "R13") (pin "2") (pinfunction "2_2") (pintype "passive"))
    )
    (net (code "91") (name "/TRAN2A3") (class "Default")
      (node (ref "IC9") (pin "16") (pinfunction "O3_16") (pintype "open_collector"))
      (node (ref "R14") (pin "2") (pinfunction "2_2") (pintype "passive"))
    )
    (net (code "92") (name "/TRAN2A4") (class "Default")
      (node (ref "IC9") (pin "15") (pinfunction "O4_15") (pintype "open_collector"))
      (node (ref "R15") (pin "2") (pinfunction "2_2") (pintype "passive"))
    )
    (net (code "93") (name "/TRAN2A5") (class "Default")
      (node (ref "IC9") (pin "14") (pinfunction "O5_14") (pintype "open_collector"))
      (node (ref "R16") (pin "2") (pinfunction "2_2") (pintype "passive"))
    )
    (net (code "94") (name "/TRAN2A6") (class "Default")
      (node (ref "IC9") (pin "13") (pinfunction "O6_13") (pintype "open_collector"))
      (node (ref "R17") (pin "2") (pinfunction "2_2") (pintype "passive"))
    )
    (net (code "95") (name "/TRAN2A7") (class "Default")
      (node (ref "IC9") (pin "12") (pinfunction "O7_12") (pintype "open_collector"))
      (node (ref "R18") (pin "2") (pinfunction "2_2") (pintype "passive"))
    )
    (net (code "96") (name "/TRAN2A8") (class "Default")
      (node (ref "IC9") (pin "11") (pinfunction "O8_11") (pintype "open_collector"))
      (node (ref "R19") (pin "2") (pinfunction "2_2") (pintype "passive"))
    )
    (net (code "97") (name "/TRAN2B1") (class "Default")
      (node (ref "IC11") (pin "18") (pinfunction "O1_18") (pintype "open_collector"))
      (node (ref "R28") (pin "2") (pinfunction "2_2") (pintype "passive"))
    )
    (net (code "98") (name "/TRAN2B2") (class "Default")
      (node (ref "IC11") (pin "17") (pinfunction "O2_17") (pintype "open_collector"))
      (node (ref "R29") (pin "2") (pinfunction "2_2") (pintype "passive"))
    )
    (net (code "99") (name "/TRAN2B3") (class "Default")
      (node (ref "IC11") (pin "16") (pinfunction "O3_16") (pintype "open_collector"))
      (node (ref "R30") (pin "2") (pinfunction "2_2") (pintype "passive"))
    )
    (net (code "100") (name "/TRAN2B4") (class "Default")
      (node (ref "IC11") (pin "15") (pinfunction "O4_15") (pintype "open_collector"))
      (node (ref "R31") (pin "2") (pinfunction "2_2") (pintype "passive"))
    )
    (net (code "101") (name "/TRAN2B5") (class "Default")
      (node (ref "IC11") (pin "14") (pinfunction "O5_14") (pintype "open_collector"))
      (node (ref "R32") (pin "2") (pinfunction "2_2") (pintype "passive"))
    )
    (net (code "102") (name "/TRAN2B6") (class "Default")
      (node (ref "IC11") (pin "13") (pinfunction "O6_13") (pintype "open_collector"))
      (node (ref "R33") (pin "2") (pinfunction "2_2") (pintype "passive"))
    )
    (net (code "103") (name "/TRAN2B7") (class "Default")
      (node (ref "IC11") (pin "12") (pinfunction "O7_12") (pintype "open_collector"))
      (node (ref "R34") (pin "2") (pinfunction "2_2") (pintype "passive"))
    )
    (net (code "104") (name "/TRAN2B8") (class "Default")
      (node (ref "IC11") (pin "11") (pinfunction "O8_11") (pintype "open_collector"))
      (node (ref "R35") (pin "2") (pinfunction "2_2") (pintype "passive"))
    )
    (net (code "105") (name "GND") (class "Default")
      (node (ref "BRIGHTNESS") (pin "1") (pinfunction "A_1") (pintype "passive"))
      (node (ref "C1") (pin "1") (pinfunction "1_1") (pintype "passive"))
      (node (ref "C2") (pin "1") (pinfunction "1_1") (pintype "passive"))
      (node (ref "DOWN") (pin "1") (pinfunction "S_1") (pintype "passive"))
      (node (ref "IC1") (pin "22") (pinfunction "GND_22") (pintype "power_in"))
      (node (ref "IC1") (pin "8") (pinfunction "GND_8") (pintype "power_in"))
      (node (ref "IC10") (pin "9") (pinfunction "GND_9") (pintype "power_in"))
      (node (ref "IC11") (pin "9") (pinfunction "GND_9") (pintype "power_in"))
      (node (ref "IC2") (pin "12") (pinfunction "VSS_12") (pintype "power_in"))
      (node (ref "IC2") (pin "23") (pinfunction "INH_23") (pintype "input"))
      (node (ref "IC3") (pin "12") (pinfunction "VSS_12") (pintype "power_in"))
      (node (ref "IC3") (pin "23") (pinfunction "INH_23") (pintype "input"))
      (node (ref "IC4") (pin "8") (pinfunction "VSS_8") (pintype "power_in"))
      (node (ref "IC5") (pin "8") (pinfunction "VSS_8") (pintype "power_in"))
      (node (ref "IC6") (pin "8") (pinfunction "VSS_8") (pintype "power_in"))
      (node (ref "IC7") (pin "8") (pinfunction "VSS_8") (pintype "power_in"))
      (node (ref "IC8") (pin "9") (pinfunction "GND_9") (pintype "power_in"))
      (node (ref "IC9") (pin "9") (pinfunction "GND_9") (pintype "power_in"))
      (node (ref "J9") (pin "1") (pinfunction "1_1") (pintype "passive"))
      (node (ref "LEFT") (pin "1") (pinfunction "S_1") (pintype "passive"))
      (node (ref "PL1") (pin "1") (pinfunction "A_1") (pintype "passive"))
      (node (ref "PL2") (pin "1") (pinfunction "A_1") (pintype "passive"))
      (node (ref "RIGHT") (pin "1") (pinfunction "S_1") (pintype "passive"))
      (node (ref "UP") (pin "1") (pinfunction "S_1") (pintype "passive"))
    )
    (net (code "106") (name "Net-(BRIGHTNESS-S)") (class "Default")
      (node (ref "BRIGHTNESS") (pin "2") (pinfunction "S_2") (pintype "passive"))
      (node (ref "IC1") (pin "25") (pinfunction "PC2(ADC2)_25") (pintype "bidirectional"))
    )
    (net (code "107") (name "Net-(DOWN-P1)") (class "Default")
      (node (ref "DOWN") (pin "4") (pinfunction "P1_4") (pintype "passive"))
      (node (ref "R3") (pin "1") (pinfunction "1_1") (pintype "passive"))
    )
    (net (code "108") (name "Net-(IC1-PB4(MISO))") (class "Default")
      (node (ref "IC1") (pin "18") (pinfunction "PB4(MISO)_18") (pintype "bidirectional"))
      (node (ref "IC2") (pin "1") (pinfunction "ST_1") (pintype "input"))
    )
    (net (code "109") (name "Net-(IC1-PB5(SCK))") (class "Default")
      (node (ref "IC1") (pin "19") (pinfunction "PB5(SCK)_19") (pintype "bidirectional"))
      (node (ref "IC3") (pin "1") (pinfunction "ST_1") (pintype "input"))
    )
    (net (code "110") (name "Net-(IC1-PB6(XTAL1{slash}TOSC1))") (class "Default")
      (node (ref "C1") (pin "2") (pinfunction "2_2") (pintype "passive"))
      (node (ref "IC1") (pin "9") (pinfunction "PB6(XTAL1/TOSC1)_9") (pintype "bidirectional"))
      (node (ref "Q1") (pin "2") (pinfunction "2_2") (pintype "passive"))
    )
    (net (code "111") (name "Net-(IC1-PB7(XTAL2{slash}TOSC2))") (class "Default")
      (node (ref "C2") (pin "2") (pinfunction "2_2") (pintype "passive"))
      (node (ref "IC1") (pin "10") (pinfunction "PB7(XTAL2/TOSC2)_10") (pintype "bidirectional"))
      (node (ref "Q1") (pin "1") (pinfunction "1_1") (pintype "passive"))
    )
    (net (code "112") (name "Net-(IC1-PC0(ADC0))") (class "Default")
      (node (ref "IC1") (pin "23") (pinfunction "PC0(ADC0)_23") (pintype "bidirectional"))
      (node (ref "PL1") (pin "2") (pinfunction "S_2") (pintype "passive"))
    )
    (net (code "113") (name "Net-(IC1-PC1(ADC1))") (class "Default")
      (node (ref "IC1") (pin "24") (pinfunction "PC1(ADC1)_24") (pintype "bidirectional"))
      (node (ref "PL2") (pin "2") (pinfunction "S_2") (pintype "passive"))
    )
    (net (code "114") (name "Net-(IC1-PC3(ADC3))") (class "Default")
      (node (ref "IC1") (pin "26") (pinfunction "PC3(ADC3)_26") (pintype "bidirectional"))
      (node (ref "R1") (pin "2") (pinfunction "2_2") (pintype "passive"))
    )
    (net (code "115") (name "Net-(IC1-PC4(ADC4{slash}SDA))") (class "Default")
      (node (ref "IC1") (pin "27") (pinfunction "PC4(ADC4/SDA)_27") (pintype "bidirectional"))
      (node (ref "R2") (pin "2") (pinfunction "2_2") (pintype "passive"))
    )
    (net (code "116") (name "Net-(IC1-PD0(RXD))") (class "Default")
      (node (ref "IC1") (pin "2") (pinfunction "PD0(RXD)_2") (pintype "bidirectional"))
      (node (ref "IC4") (pin "15") (pinfunction "OE_15") (pintype "input"))
      (node (ref "IC5") (pin "15") (pinfunction "OE_15") (pintype "input"))
      (node (ref "IC6") (pin "1") (pinfunction "STR_1") (pintype "input"))
      (node (ref "IC7") (pin "1") (pinfunction "STR_1") (pintype "input"))
    )
    (net (code "117") (name "Net-(IC1-PD1(TXD))") (class "Default")
      (node (ref "IC1") (pin "3") (pinfunction "PD1(TXD)_3") (pintype "bidirectional"))
      (node (ref "IC4") (pin "3") (pinfunction "CLK_3") (pintype "input"))
      (node (ref "IC5") (pin "3") (pinfunction "CLK_3") (pintype "input"))
      (node (ref "IC6") (pin "2") (pinfunction "D_2") (pintype "input"))
      (node (ref "IC7") (pin "2") (pinfunction "D_2") (pintype "input"))
    )
    (net (code "118") (name "Net-(IC1-PD2(INT0))") (class "Default")
      (node (ref "IC1") (pin "4") (pinfunction "PD2(INT0)_4") (pintype "bidirectional"))
      (node (ref "IC4") (pin "2") (pinfunction "D_2") (pintype "input"))
      (node (ref "IC5") (pin "2") (pinfunction "D_2") (pintype "input"))
      (node (ref "IC6") (pin "3") (pinfunction "CLK_3") (pintype "input"))
      (node (ref "IC7") (pin "3") (pinfunction "CLK_3") (pintype "input"))
    )
    (net (code "119") (name "Net-(IC1-PD3(INT1))") (class "Default")
      (node (ref "IC1") (pin "5") (pinfunction "PD3(INT1)_5") (pintype "bidirectional"))
      (node (ref "IC4") (pin "1") (pinfunction "STR_1") (pintype "input"))
      (node (ref "IC5") (pin "1") (pinfunction "STR_1") (pintype "input"))
      (node (ref "IC6") (pin "15") (pinfunction "OE_15") (pintype "input"))
      (node (ref "IC7") (pin "15") (pinfunction "OE_15") (pintype "input"))
    )
    (net (code "120") (name "Net-(J1-Pad1)") (class "Default")
      (node (ref "J1") (pin "1") (pinfunction "1_1") (pintype "passive"))
      (node (ref "R11") (pin "1") (pinfunction "1_1") (pintype "passive"))
    )
    (net (code "121") (name "Net-(J1-Pad2)") (class "Default")
      (node (ref "J1") (pin "2") (pinfunction "2_2") (pintype "passive"))
      (node (ref "R10") (pin "1") (pinfunction "1_1") (pintype "passive"))
    )
    (net (code "122") (name "Net-(J1-Pad3)") (class "Default")
      (node (ref "J1") (pin "3") (pinfunction "3_3") (pintype "passive"))
      (node (ref "R9") (pin "1") (pinfunction "1_1") (pintype "passive"))
    )
    (net (code "123") (name "Net-(J1-Pad4)") (class "Default")
      (node (ref "J1") (pin "4") (pinfunction "4_4") (pintype "passive"))
      (node (ref "R8") (pin "1") (pinfunction "1_1") (pintype "passive"))
    )
    (net (code "124") (name "Net-(J1-Pad5)") (class "Default")
      (node (ref "J1") (pin "5") (pinfunction "5_5") (pintype "passive"))
      (node (ref "R7") (pin "1") (pinfunction "1_1") (pintype "passive"))
    )
    (net (code "125") (name "Net-(J1-Pad6)") (class "Default")
      (node (ref "J1") (pin "6") (pinfunction "6_6") (pintype "passive"))
      (node (ref "R6") (pin "1") (pinfunction "1_1") (pintype "passive"))
    )
    (net (code "126") (name "Net-(J1-Pad7)") (class "Default")
      (node (ref "J1") (pin "7") (pinfunction "7_7") (pintype "passive"))
      (node (ref "R5") (pin "1") (pinfunction "1_1") (pintype "passive"))
    )
    (net (code "127") (name "Net-(J1-Pad8)") (class "Default")
      (node (ref "J1") (pin "8") (pinfunction "8_8") (pintype "passive"))
      (node (ref "R4") (pin "1") (pinfunction "1_1") (pintype "passive"))
    )
    (net (code "128") (name "Net-(J2-Pad1)") (class "Default")
      (node (ref "J2") (pin "1") (pinfunction "1_1") (pintype "passive"))
      (node (ref "R19") (pin "1") (pinfunction "1_1") (pintype "passive"))
    )
    (net (code "129") (name "Net-(J2-Pad2)") (class "Default")
      (node (ref "J2") (pin "2") (pinfunction "2_2") (pintype "passive"))
      (node (ref "R18") (pin "1") (pinfunction "1_1") (pintype "passive"))
    )
    (net (code "130") (name "Net-(J2-Pad3)") (class "Default")
      (node (ref "J2") (pin "3") (pinfunction "3_3") (pintype "passive"))
      (node (ref "R17") (pin "1") (pinfunction "1_1") (pintype "passive"))
    )
    (net (code "131") (name "Net-(J2-Pad4)") (class "Default")
      (node (ref "J2") (pin "4") (pinfunction "4_4") (pintype "passive"))
      (node (ref "R16") (pin "1") (pinfunction "1_1") (pintype "passive"))
    )
    (net (code "132") (name "Net-(J2-Pad5)") (class "Default")
      (node (ref "J2") (pin "5") (pinfunction "5_5") (pintype "passive"))
      (node (ref "R15") (pin "1") (pinfunction "1_1") (pintype "passive"))
    )
    (net (code "133") (name "Net-(J2-Pad6)") (class "Default")
      (node (ref "J2") (pin "6") (pinfunction "6_6") (pintype "passive"))
      (node (ref "R14") (pin "1") (pinfunction "1_1") (pintype "passive"))
    )
    (net (code "134") (name "Net-(J2-Pad7)") (class "Default")
      (node (ref "J2") (pin "7") (pinfunction "7_7") (pintype "passive"))
      (node (ref "R13") (pin "1") (pinfunction "1_1") (pintype "passive"))
    )
    (net (code "135") (name "Net-(J2-Pad8)") (class "Default")
      (node (ref "J2") (pin "8") (pinfunction "8_8") (pintype "passive"))
      (node (ref "R12") (pin "1") (pinfunction "1_1") (pintype "passive"))
    )
    (net (code "136") (name "Net-(J5-Pad1)") (class "Default")
      (node (ref "J5") (pin "1") (pinfunction "1_1") (pintype "passive"))
      (node (ref "R27") (pin "1") (pinfunction "1_1") (pintype "passive"))
    )
    (net (code "137") (name "Net-(J5-Pad2)") (class "Default")
      (node (ref "J5") (pin "2") (pinfunction "2_2") (pintype "passive"))
      (node (ref "R26") (pin "1") (pinfunction "1_1") (pintype "passive"))
    )
    (net (code "138") (name "Net-(J5-Pad3)") (class "Default")
      (node (ref "J5") (pin "3") (pinfunction "3_3") (pintype "passive"))
      (node (ref "R25") (pin "1") (pinfunction "1_1") (pintype "passive"))
    )
    (net (code "139") (name "Net-(J5-Pad4)") (class "Default")
      (node (ref "J5") (pin "4") (pinfunction "4_4") (pintype "passive"))
      (node (ref "R24") (pin "1") (pinfunction "1_1") (pintype "passive"))
    )
    (net (code "140") (name "Net-(J5-Pad5)") (class "Default")
      (node (ref "J5") (pin "5") (pinfunction "5_5") (pintype "passive"))
      (node (ref "R23") (pin "1") (pinfunction "1_1") (pintype "passive"))
    )
    (net (code "141") (name "Net-(J5-Pad6)") (class "Default")
      (node (ref "J5") (pin "6") (pinfunction "6_6") (pintype "passive"))
      (node (ref "R22") (pin "1") (pinfunction "1_1") (pintype "passive"))
    )
    (net (code "142") (name "Net-(J5-Pad7)") (class "Default")
      (node (ref "J5") (pin "7") (pinfunction "7_7") (pintype "passive"))
      (node (ref "R21") (pin "1") (pinfunction "1_1") (pintype "passive"))
    )
    (net (code "143") (name "Net-(J5-Pad8)") (class "Default")
      (node (ref "J5") (pin "8") (pinfunction "8_8") (pintype "passive"))
      (node (ref "R20") (pin "1") (pinfunction "1_1") (pintype "passive"))
    )
    (net (code "144") (name "Net-(J6-Pad1)") (class "Default")
      (node (ref "J6") (pin "1") (pinfunction "1_1") (pintype "passive"))
      (node (ref "R35") (pin "1") (pinfunction "1_1") (pintype "passive"))
    )
    (net (code "145") (name "Net-(J6-Pad2)") (class "Default")
      (node (ref "J6") (pin "2") (pinfunction "2_2") (pintype "passive"))
      (node (ref "R34") (pin "1") (pinfunction "1_1") (pintype "passive"))
    )
    (net (code "146") (name "Net-(J6-Pad3)") (class "Default")
      (node (ref "J6") (pin "3") (pinfunction "3_3") (pintype "passive"))
      (node (ref "R33") (pin "1") (pinfunction "1_1") (pintype "passive"))
    )
    (net (code "147") (name "Net-(J6-Pad4)") (class "Default")
      (node (ref "J6") (pin "4") (pinfunction "4_4") (pintype "passive"))
      (node (ref "R32") (pin "1") (pinfunction "1_1") (pintype "passive"))
    )
    (net (code "148") (name "Net-(J6-Pad5)") (class "Default")
      (node (ref "J6") (pin "5") (pinfunction "5_5") (pintype "passive"))
      (node (ref "R31") (pin "1") (pinfunction "1_1") (pintype "passive"))
    )
    (net (code "149") (name "Net-(J6-Pad6)") (class "Default")
      (node (ref "J6") (pin "6") (pinfunction "6_6") (pintype "passive"))
      (node (ref "R30") (pin "1") (pinfunction "1_1") (pintype "passive"))
    )
    (net (code "150") (name "Net-(J6-Pad7)") (class "Default")
      (node (ref "J6") (pin "7") (pinfunction "7_7") (pintype "passive"))
      (node (ref "R29") (pin "1") (pinfunction "1_1") (pintype "passive"))
    )
    (net (code "151") (name "Net-(J6-Pad8)") (class "Default")
      (node (ref "J6") (pin "8") (pinfunction "8_8") (pintype "passive"))
      (node (ref "R28") (pin "1") (pinfunction "1_1") (pintype "passive"))
    )
    (net (code "152") (name "Net-(LEFT-P)") (class "Default")
      (node (ref "LEFT") (pin "3") (pinfunction "P_3") (pintype "passive"))
      (node (ref "R36") (pin "1") (pinfunction "1_1") (pintype "passive"))
    )
    (net (code "153") (name "Net-(RIGHT-P)") (class "Default")
      (node (ref "R2") (pin "1") (pinfunction "1_1") (pintype "passive"))
      (node (ref "R36") (pin "2") (pinfunction "2_2") (pintype "passive"))
      (node (ref "RIGHT") (pin "3") (pinfunction "P_3") (pintype "passive"))
    )
    (net (code "154") (name "Net-(UP-P)") (class "Default")
      (node (ref "R1") (pin "1") (pinfunction "1_1") (pintype "passive"))
      (node (ref "R3") (pin "2") (pinfunction "2_2") (pintype "passive"))
      (node (ref "UP") (pin "3") (pinfunction "P_3") (pintype "passive"))
    )
    (net (code "155") (name "VCC") (class "Default")
      (node (ref "BRIGHTNESS") (pin "3") (pinfunction "E_3") (pintype "passive"))
      (node (ref "IC1") (pin "20") (pinfunction "AVCC_20") (pintype "power_in"))
      (node (ref "IC1") (pin "7") (pinfunction "VCC_7") (pintype "power_in"))
      (node (ref "IC10") (pin "10") (pinfunction "CD+_10") (pintype "passive"))
      (node (ref "IC11") (pin "10") (pinfunction "CD+_10") (pintype "passive"))
      (node (ref "IC2") (pin "24") (pinfunction "VDD_24") (pintype "power_in"))
      (node (ref "IC3") (pin "24") (pinfunction "VDD_24") (pintype "power_in"))
      (node (ref "IC4") (pin "16") (pinfunction "VDD_16") (pintype "power_in"))
      (node (ref "IC5") (pin "16") (pinfunction "VDD_16") (pintype "power_in"))
      (node (ref "IC6") (pin "16") (pinfunction "VDD_16") (pintype "power_in"))
      (node (ref "IC7") (pin "16") (pinfunction "VDD_16") (pintype "power_in"))
      (node (ref "IC8") (pin "10") (pinfunction "CD+_10") (pintype "passive"))
      (node (ref "IC9") (pin "10") (pinfunction "CD+_10") (pintype "passive"))
      (node (ref "J9") (pin "2") (pinfunction "2_2") (pintype "passive"))
      (node (ref "J9") (pin "3") (pinfunction "3_3") (pintype "passive"))
      (node (ref "PL1") (pin "3") (pinfunction "E_3") (pintype "passive"))
      (node (ref "PL2") (pin "3") (pinfunction "E_3") (pintype "passive"))
    )
    (net (code "156") (name "unconnected-(DOWN-P-Pad3)") (class "Default")
      (node (ref "DOWN") (pin "3") (pinfunction "P_3") (pintype "passive"))
    )
    (net (code "157") (name "unconnected-(DOWN-S1-Pad2)") (class "Default")
      (node (ref "DOWN") (pin "2") (pinfunction "S1_2") (pintype "passive"))
    )
    (net (code "158") (name "unconnected-(IC1-AREF-Pad21)") (class "Default")
      (node (ref "IC1") (pin "21") (pinfunction "AREF_21") (pintype "passive"))
    )
    (net (code "159") (name "unconnected-(IC1-PC5(ADC5{slash}SCL)-Pad28)") (class "Default")
      (node (ref "IC1") (pin "28") (pinfunction "PC5(ADC5/SCL)_28") (pintype "bidirectional"))
    )
    (net (code "160") (name "unconnected-(IC1-PC6({slash}RESET)-Pad1)") (class "Default")
      (node (ref "IC1") (pin "1") (pinfunction "PC6(/RESET)_1") (pintype "bidirectional"))
    )
    (net (code "161") (name "unconnected-(IC4A-QS*-Pad10)") (class "Default")
      (node (ref "IC4") (pin "10") (pinfunction "QS*_10") (pintype "output"))
    )
    (net (code "162") (name "unconnected-(IC4A-QS-Pad9)") (class "Default")
      (node (ref "IC4") (pin "9") (pinfunction "QS_9") (pintype "output"))
    )
    (net (code "163") (name "unconnected-(IC5A-QS*-Pad10)") (class "Default")
      (node (ref "IC5") (pin "10") (pinfunction "QS*_10") (pintype "output"))
    )
    (net (code "164") (name "unconnected-(IC5A-QS-Pad9)") (class "Default")
      (node (ref "IC5") (pin "9") (pinfunction "QS_9") (pintype "output"))
    )
    (net (code "165") (name "unconnected-(IC6A-QS*-Pad10)") (class "Default")
      (node (ref "IC6") (pin "10") (pinfunction "QS*_10") (pintype "output"))
    )
    (net (code "166") (name "unconnected-(IC6A-QS-Pad9)") (class "Default")
      (node (ref "IC6") (pin "9") (pinfunction "QS_9") (pintype "output"))
    )
    (net (code "167") (name "unconnected-(IC7A-QS*-Pad10)") (class "Default")
      (node (ref "IC7") (pin "10") (pinfunction "QS*_10") (pintype "output"))
    )
    (net (code "168") (name "unconnected-(IC7A-QS-Pad9)") (class "Default")
      (node (ref "IC7") (pin "9") (pinfunction "QS_9") (pintype "output"))
    )
    (net (code "169") (name "unconnected-(LEFT-P1-Pad4)") (class "Default")
      (node (ref "LEFT") (pin "4") (pinfunction "P1_4") (pintype "passive"))
    )
    (net (code "170") (name "unconnected-(LEFT-S1-Pad2)") (class "Default")
      (node (ref "LEFT") (pin "2") (pinfunction "S1_2") (pintype "passive"))
    )
    (net (code "171") (name "unconnected-(RIGHT-P1-Pad4)") (class "Default")
      (node (ref "RIGHT") (pin "4") (pinfunction "P1_4") (pintype "passive"))
    )
    (net (code "172") (name "unconnected-(RIGHT-S1-Pad2)") (class "Default")
      (node (ref "RIGHT") (pin "2") (pinfunction "S1_2") (pintype "passive"))
    )
    (net (code "173") (name "unconnected-(UP-P1-Pad4)") (class "Default")
      (node (ref "UP") (pin "4") (pinfunction "P1_4") (pintype "passive"))
    )
    (net (code "174") (name "unconnected-(UP-S1-Pad2)") (class "Default")
      (node (ref "UP") (pin "2") (pinfunction "S1_2") (pintype "passive"))
    )
  )
)
